# with_direction.net
KiCad netlist of a schematic drawn in EAGLE
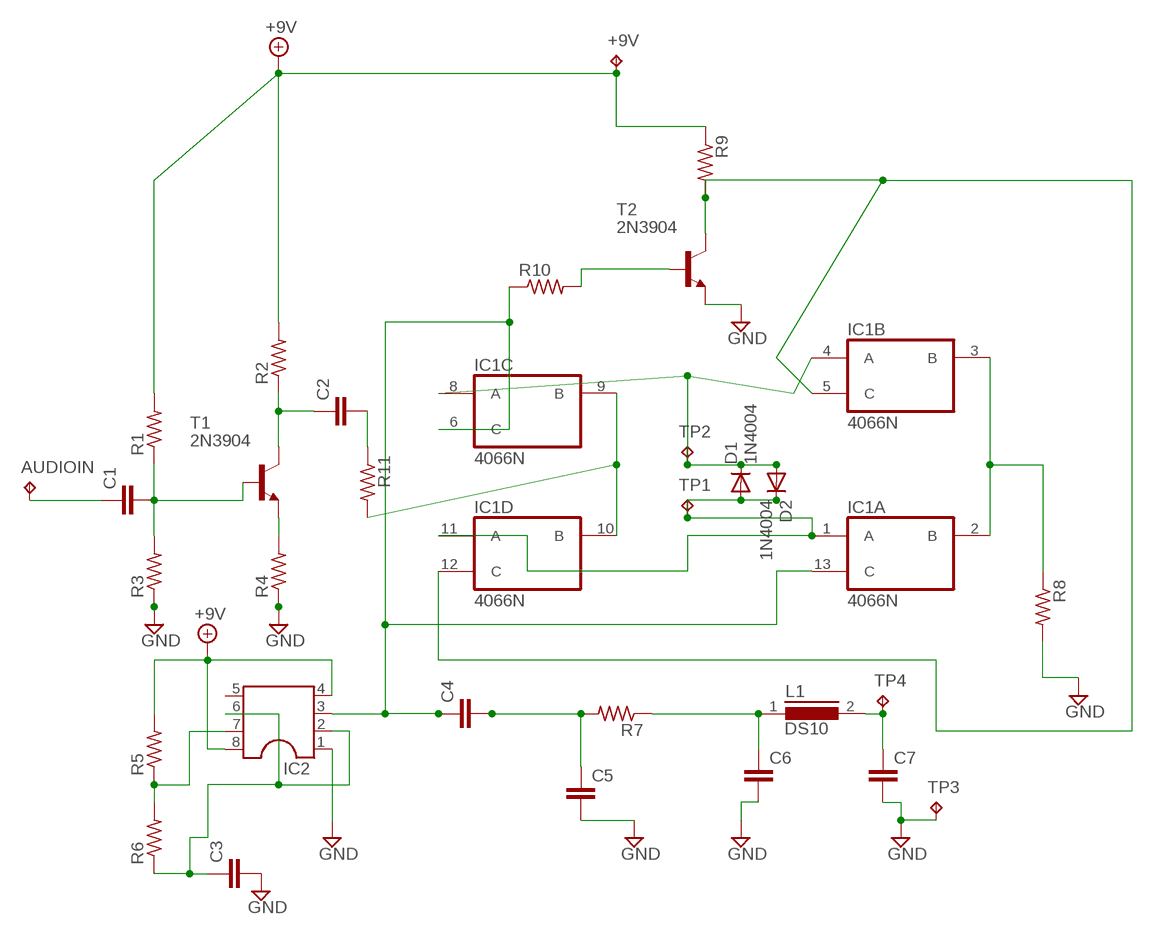
[diagram p0: schematic, sheet 1]

(export (version "E")
  (design (tool "Eeschema 10.0.6"))
  (components
    (comp (ref "+9V")
      (value "TPPAD1-17")
      (footprint "eagle-import:P1-17")
      (libsource (lib "eagle-import") (part "TPPAD1-17"))
    )
    (comp (ref "AUDIOIN")
      (value "TPPAD1-17")
      (footprint "eagle-import:P1-17")
      (libsource (lib "eagle-import") (part "TPPAD1-17"))
    )
    (comp (ref "C1")
      (value "C10/5")
      (footprint "eagle-import:C10B5")
      (libsource (lib "eagle-import") (part "C10/5"))
    )
    (comp (ref "C2")
      (value "C10/5")
      (footprint "eagle-import:C10B5")
      (libsource (lib "eagle-import") (part "C10/5"))
    )
    (comp (ref "C3")
      (value "C5/2.5")
      (footprint "eagle-import:C5B2.5")
      (libsource (lib "eagle-import") (part "C5/2.5"))
    )
    (comp (ref "C4")
      (value "C5/2.5")
      (footprint "eagle-import:C5B2.5")
      (libsource (lib "eagle-import") (part "C5/2.5"))
    )
    (comp (ref "C5")
      (value "C5/3")
      (footprint "eagle-import:C5B3")
      (libsource (lib "eagle-import") (part "C5/3"))
    )
    (comp (ref "C6")
      (value "C5/3")
      (footprint "eagle-import:C5B3")
      (libsource (lib "eagle-import") (part "C5/3"))
    )
    (comp (ref "C7")
      (value "C10/5")
      (footprint "eagle-import:C10B5")
      (libsource (lib "eagle-import") (part "C10/5"))
    )
    (comp (ref "D1")
      (value "1N4004")
      (footprint "eagle-import:DO41-10")
      (libsource (lib "eagle-import") (part "1N4004"))
    )
    (comp (ref "D2")
      (value "1N4004")
      (footprint "eagle-import:DO41-10")
      (libsource (lib "eagle-import") (part "1N4004"))
    )
    (comp (ref "IC1")
      (value "4066N")
      (footprint "eagle-import:DIL14")
      (libsource (lib "eagle-import") (part "4066N"))
    )
    (comp (ref "IC2")
      (value "DIL8S")
      (footprint "eagle-import:SOCKET-08")
      (libsource (lib "eagle-import") (part "DIL8S"))
    )
    (comp (ref "L1")
      (value "DS10")
      (footprint "eagle-import:DS10")
      (libsource (lib "eagle-import") (part "DS10"))
    )
    (comp (ref "R1")
      (value "R-US_0207/10")
      (footprint "eagle-import:0207_10")
      (libsource (lib "eagle-import") (part "R-US_0207/10"))
    )
    (comp (ref "R2")
      (value "R-US_0207/10")
      (footprint "eagle-import:0207_10")
      (libsource (lib "eagle-import") (part "R-US_0207/10"))
    )
    (comp (ref "R3")
      (value "R-US_0207/10")
      (footprint "eagle-import:0207_10")
      (libsource (lib "eagle-import") (part "R-US_0207/10"))
    )
    (comp (ref "R4")
      (value "R-US_0207/10")
      (footprint "eagle-import:0207_10")
      (libsource (lib "eagle-import") (part "R-US_0207/10"))
    )
    (comp (ref "R5")
      (value "R-US_0207/10")
      (footprint "eagle-import:0207_10")
      (libsource (lib "eagle-import") (part "R-US_0207/10"))
    )
    (comp (ref "R6")
      (value "R-US_0207/10")
      (footprint "eagle-import:0207_10")
      (libsource (lib "eagle-import") (part "R-US_0207/10"))
    )
    (comp (ref "R7")
      (value "R-US_0207/10")
      (footprint "eagle-import:0207_10")
      (libsource (lib "eagle-import") (part "R-US_0207/10"))
    )
    (comp (ref "R8")
      (value "R-US_0207/10")
      (footprint "eagle-import:0207_10")
      (libsource (lib "eagle-import") (part "R-US_0207/10"))
    )
    (comp (ref "R9")
      (value "R-US_0207/15")
      (footprint "eagle-import:0207_15")
      (libsource (lib "eagle-import") (part "R-US_0207/15"))
    )
    (comp (ref "R10")
      (value "R-US_0207/10")
      (footprint "eagle-import:0207_10")
      (libsource (lib "eagle-import") (part "R-US_0207/10"))
    )
    (comp (ref "R11")
      (value "R-US_0207/15")
      (footprint "eagle-import:0207_15")
      (libsource (lib "eagle-import") (part "R-US_0207/15"))
    )
    (comp (ref "T1")
      (value "2N3904")
      (footprint "eagle-import:TO92")
      (libsource (lib "eagle-import") (part "2N3904"))
    )
    (comp (ref "T2")
      (value "2N3904")
      (footprint "eagle-import:TO92")
      (libsource (lib "eagle-import") (part "2N3904"))
    )
    (comp (ref "TP1")
      (value "TPPAD1-17")
      (footprint "eagle-import:P1-17")
      (libsource (lib "eagle-import") (part "TPPAD1-17"))
    )
    (comp (ref "TP2")
      (value "TPPAD1-17")
      (footprint "eagle-import:P1-17")
      (libsource (lib "eagle-import") (part "TPPAD1-17"))
    )
    (comp (ref "TP3")
      (value "TPPAD1-17Y")
      (footprint "eagle-import:P1-17Y")
      (libsource (lib "eagle-import") (part "TPPAD1-17Y"))
    )
    (comp (ref "TP4")
      (value "TPPAD1-17Y")
      (footprint "eagle-import:P1-17Y")
      (libsource (lib "eagle-import") (part "TPPAD1-17Y"))
    )
  )
  (nets
    (net (code "1") (name "+9V") (class "Default")
      (node (ref "+9V") (pin "TP") (pinfunction "TP_TP") (pintype "input"))
      (node (ref "IC2") (pin "4") (pinfunction "4_4") (pintype "passive"))
      (node (ref "IC2") (pin "8") (pinfunction "8_8") (pintype "passive"))
      (node (ref "R1") (pin "2") (pinfunction "2_2") (pintype "passive"))
      (node (ref "R2") (pin "2") (pinfunction "2_2") (pintype "passive"))
      (node (ref "R5") (pin "2") (pinfunction "2_2") (pintype "passive"))
      (node (ref "R9") (pin "1") (pinfunction "1_1") (pintype "passive"))
    )
    (net (code "2") (name "GND") (class "Default")
      (node (ref "C3") (pin "2") (pinfunction "2_2") (pintype "passive"))
      (node (ref "C5") (pin "2") (pinfunction "2_2") (pintype "passive"))
      (node (ref "C6") (pin "2") (pinfunction "2_2") (pintype "passive"))
      (node (ref "C7") (pin "2") (pinfunction "2_2") (pintype "passive"))
      (node (ref "IC2") (pin "1") (pinfunction "1_1") (pintype "passive"))
      (node (ref "R3") (pin "1") (pinfunction "1_1") (pintype "passive"))
      (node (ref "R4") (pin "1") (pinfunction "1_1") (pintype "passive"))
      (node (ref "R8") (pin "2") (pinfunction "2_2") (pintype "passive"))
      (node (ref "T2") (pin "3") (pinfunction "E_3") (pintype "passive"))
      (node (ref "TP3") (pin "TP") (pinfunction "TP_TP") (pintype "input"))
    )
    (net (code "3") (name "Net-(AUDIOIN-PadTP)") (class "Default")
      (node (ref "AUDIOIN") (pin "TP") (pinfunction "TP_TP") (pintype "input"))
      (node (ref "C1") (pin "1") (pinfunction "1_1") (pintype "passive"))
    )
    (net (code "4") (name "Net-(C2-Pad2)") (class "Default")
      (node (ref "C2") (pin "2") (pinfunction "2_2") (pintype "passive"))
      (node (ref "R11") (pin "1") (pinfunction "1_1") (pintype "passive"))
    )
    (net (code "5") (name "Net-(C3-Pad1)") (class "Default")
      (node (ref "C3") (pin "1") (pinfunction "1_1") (pintype "passive"))
      (node (ref "IC2") (pin "2") (pinfunction "2_2") (pintype "passive"))
      (node (ref "IC2") (pin "6") (pinfunction "6_6") (pintype "passive"))
      (node (ref "R6") (pin "1") (pinfunction "1_1") (pintype "passive"))
    )
    (net (code "6") (name "Net-(C4-Pad2)") (class "Default")
      (node (ref "C4") (pin "2") (pinfunction "2_2") (pintype "passive"))
      (node (ref "C5") (pin "1") (pinfunction "1_1") (pintype "passive"))
      (node (ref "R7") (pin "2") (pinfunction "2_2") (pintype "passive"))
    )
    (net (code "7") (name "Net-(C6-Pad1)") (class "Default")
      (node (ref "C6") (pin "1") (pinfunction "1_1") (pintype "passive"))
      (node (ref "L1") (pin "1") (pinfunction "1_1") (pintype "passive"))
      (node (ref "R7") (pin "1") (pinfunction "1_1") (pintype "passive"))
    )
    (net (code "8") (name "Net-(C7-Pad1)") (class "Default")
      (node (ref "C7") (pin "1") (pinfunction "1_1") (pintype "passive"))
      (node (ref "L1") (pin "2") (pinfunction "2_2") (pintype "passive"))
      (node (ref "TP4") (pin "TP") (pinfunction "TP_TP") (pintype "input"))
    )
    (net (code "9") (name "Net-(IC1A-A)") (class "Default")
      (node (ref "D1") (pin "A") (pinfunction "A_A") (pintype "passive"))
      (node (ref "D2") (pin "C") (pinfunction "C_C") (pintype "passive"))
      (node (ref "IC1") (pin "1") (pinfunction "A_1") (pintype "tri_state"))
      (node (ref "IC1") (pin "11") (pinfunction "A_11") (pintype "tri_state"))
      (node (ref "TP1") (pin "TP") (pinfunction "TP_TP") (pintype "input"))
    )
    (net (code "10") (name "Net-(IC1A-B)") (class "Default")
      (node (ref "IC1") (pin "2") (pinfunction "B_2") (pintype "tri_state"))
      (node (ref "IC1") (pin "3") (pinfunction "B_3") (pintype "tri_state"))
      (node (ref "R8") (pin "1") (pinfunction "1_1") (pintype "passive"))
    )
    (net (code "11") (name "Net-(IC1A-C)") (class "Default")
      (node (ref "C4") (pin "1") (pinfunction "1_1") (pintype "passive"))
      (node (ref "IC1") (pin "13") (pinfunction "C_13") (pintype "input"))
      (node (ref "IC1") (pin "6") (pinfunction "C_6") (pintype "input"))
      (node (ref "IC2") (pin "3") (pinfunction "3_3") (pintype "passive"))
      (node (ref "R10") (pin "1") (pinfunction "1_1") (pintype "passive"))
    )
    (net (code "12") (name "Net-(IC1B-A)") (class "Default")
      (node (ref "D1") (pin "C") (pinfunction "C_C") (pintype "passive"))
      (node (ref "D2") (pin "A") (pinfunction "A_A") (pintype "passive"))
      (node (ref "IC1") (pin "4") (pinfunction "A_4") (pintype "tri_state"))
      (node (ref "IC1") (pin "8") (pinfunction "A_8") (pintype "tri_state"))
      (node (ref "TP2") (pin "TP") (pinfunction "TP_TP") (pintype "input"))
    )
    (net (code "13") (name "Net-(IC1B-C)") (class "Default")
      (node (ref "IC1") (pin "12") (pinfunction "C_12") (pintype "input"))
      (node (ref "IC1") (pin "5") (pinfunction "C_5") (pintype "input"))
      (node (ref "R9") (pin "2") (pinfunction "2_2") (pintype "passive"))
      (node (ref "T2") (pin "1") (pinfunction "C_1") (pintype "passive"))
    )
    (net (code "14") (name "Net-(IC1C-B)") (class "Default")
      (node (ref "IC1") (pin "10") (pinfunction "B_10") (pintype "tri_state"))
      (node (ref "IC1") (pin "9") (pinfunction "B_9") (pintype "tri_state"))
      (node (ref "R11") (pin "2") (pinfunction "2_2") (pintype "passive"))
    )
    (net (code "15") (name "Net-(IC2-Pad7)") (class "Default")
      (node (ref "IC2") (pin "7") (pinfunction "7_7") (pintype "passive"))
      (node (ref "R5") (pin "1") (pinfunction "1_1") (pintype "passive"))
      (node (ref "R6") (pin "2") (pinfunction "2_2") (pintype "passive"))
    )
    (net (code "16") (name "Net-(T1-B)") (class "Default")
      (node (ref "C1") (pin "2") (pinfunction "2_2") (pintype "passive"))
      (node (ref "R1") (pin "1") (pinfunction "1_1") (pintype "passive"))
      (node (ref "R3") (pin "2") (pinfunction "2_2") (pintype "passive"))
      (node (ref "T1") (pin "2") (pinfunction "B_2") (pintype "passive"))
    )
    (net (code "17") (name "Net-(T1-C)") (class "Default")
      (node (ref "C2") (pin "1") (pinfunction "1_1") (pintype "passive"))
      (node (ref "R2") (pin "1") (pinfunction "1_1") (pintype "passive"))
      (node (ref "T1") (pin "1") (pinfunction "C_1") (pintype "passive"))
    )
    (net (code "18") (name "Net-(T1-E)") (class "Default")
      (node (ref "R4") (pin "2") (pinfunction "2_2") (pintype "passive"))
      (node (ref "T1") (pin "3") (pinfunction "E_3") (pintype "passive"))
    )
    (net (code "19") (name "Net-(T2-B)") (class "Default")
      (node (ref "R10") (pin "2") (pinfunction "2_2") (pintype "passive"))
      (node (ref "T2") (pin "2") (pinfunction "B_2") (pintype "passive"))
    )
    (net (code "20") (name "unconnected-(IC2-Pad5)") (class "Default")
      (node (ref "IC2") (pin "5") (pinfunction "5_5") (pintype "passive"))
    )
  )
)
